# AS5600_AS5601.net
KiCad netlist of a schematic drawn in Altium Designer
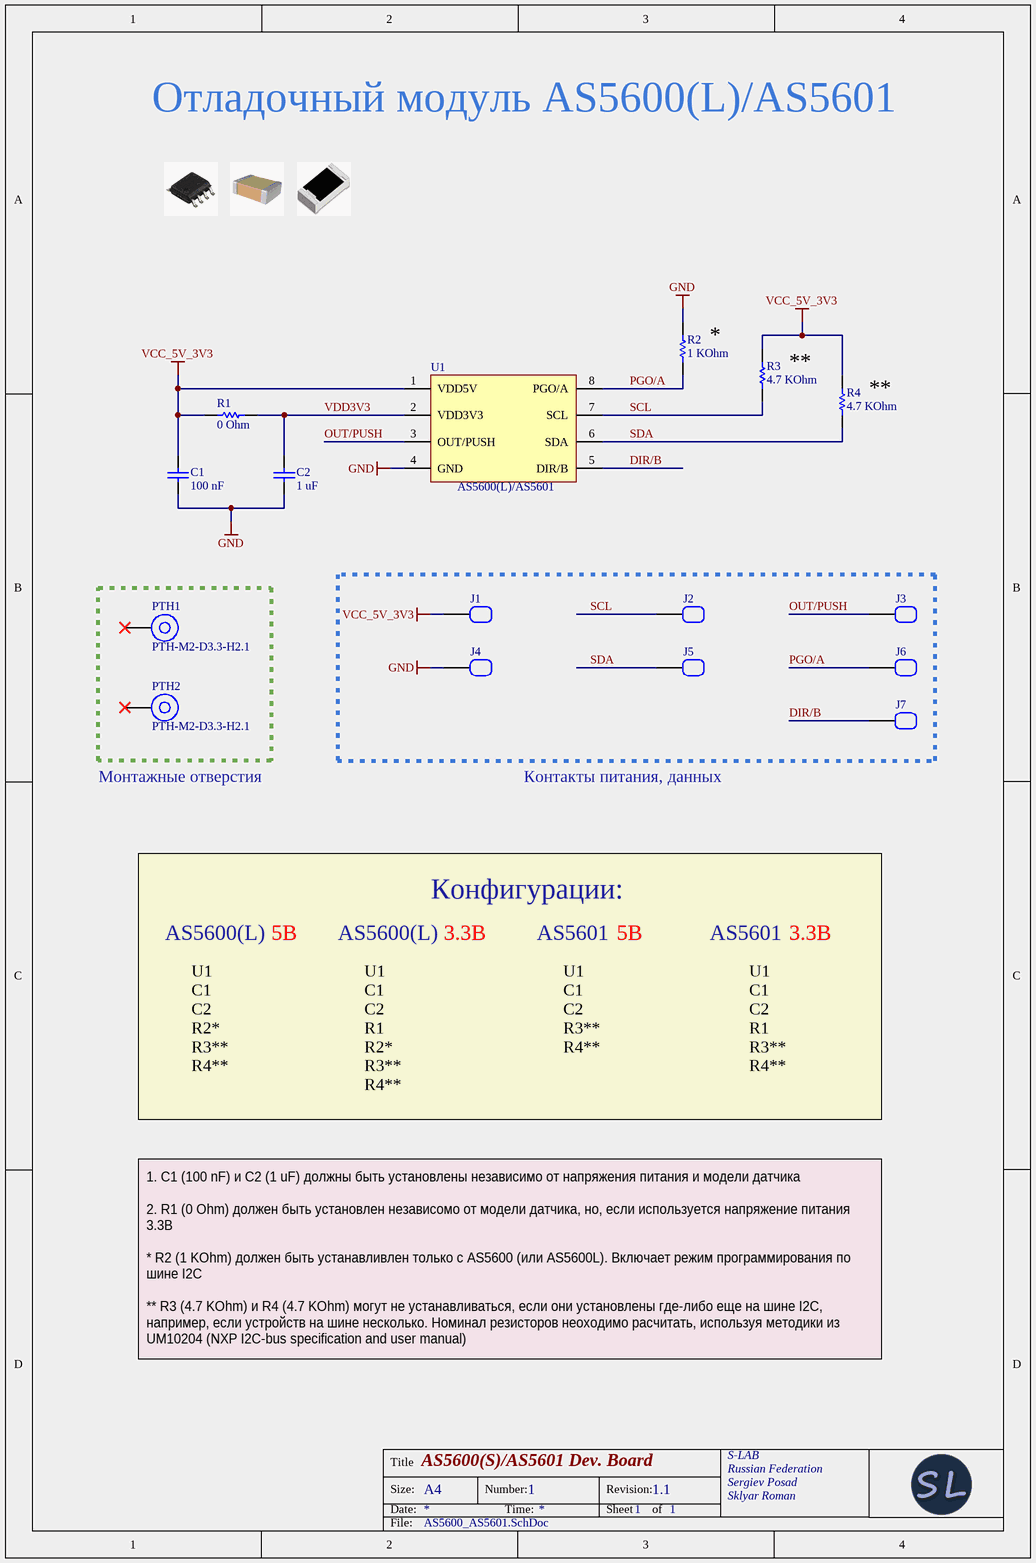
[diagram p0: AS5600_AS5601.SchDoc]

(export (version "E")
  (design (tool "Eeschema 10.0.6"))
  (components
    (comp (ref "C1")
      (value "CAP-100N")
      (footprint "CAPC0603")
      (description "Chip Capacitor, 100 nF, +/- 5%")
      (fields (field (name "TOLERANCE") "5 %") (field (name "CAPACITANCE") "100 nF"))
      (libsource (lib "Конденсаторы керамические SMD") (part "CAP-100N"))
    )
    (comp (ref "C2")
      (value "CAP-1U")
      (footprint "CAPC0603")
      (description "Chip Capacitor, 1 uF, +/- 5%")
      (fields (field (name "TOLERANCE") "5 %") (field (name "CAPACITANCE") "1 uF"))
      (libsource (lib "Конденсаторы керамические SMD") (part "CAP-1U"))
    )
    (comp (ref "J1") (value "Pad") (footprint "P_RR-1mm-2.5mm-50%") (libsource (lib "Разъемы") (part "Pad")))
    (comp (ref "J2") (value "Pad") (footprint "P_RR-1mm-2.5mm-50%") (libsource (lib "Разъемы") (part "Pad")))
    (comp (ref "J3") (value "Pad") (footprint "P_RR-1mm-2.5mm-50%") (libsource (lib "Разъемы") (part "Pad")))
    (comp (ref "J4") (value "Pad") (footprint "P_RR-1mm-2.5mm-50%") (libsource (lib "Разъемы") (part "Pad")))
    (comp (ref "J5") (value "Pad") (footprint "P_RR-1mm-2.5mm-50%") (libsource (lib "Разъемы") (part "Pad")))
    (comp (ref "J6") (value "Pad") (footprint "P_RR-1mm-2.5mm-50%") (libsource (lib "Разъемы") (part "Pad")))
    (comp (ref "J7") (value "Pad") (footprint "P_RR-1mm-2.5mm-50%") (libsource (lib "Разъемы") (part "Pad")))
    (comp (ref "PTH1")
      (value "PTH-M2-D3.3-H2.1")
      (footprint "PTH-M2-D4-H2.1")
      (libsource (lib "Разъемы") (part "PTH-M2-D4-H2.1"))
    )
    (comp (ref "PTH2")
      (value "PTH-M2-D3.3-H2.1")
      (footprint "PTH-M2-D4-H2.1")
      (libsource (lib "Разъемы") (part "PTH-M2-D4-H2.1"))
    )
    (comp (ref "R1")
      (value "RES-0")
      (footprint "RES0603")
      (description "Chip Resistor, 0 Ohm, +/- 1%")
      (fields (field (name "TOLERANCE") "1 %") (field (name "RESISTANCE") "0 Ohm"))
      (libsource (lib "Резисторы SMD") (part "RES-0"))
    )
    (comp (ref "R2")
      (value "RES-1K")
      (footprint "RES0603")
      (description "Chip Resistor, 1 KOhm, +/- 1%")
      (fields (field (name "TOLERANCE") "1 %") (field (name "RESISTANCE") "1 KOhm"))
      (libsource (lib "Резисторы SMD") (part "RES-1K"))
    )
    (comp (ref "R3")
      (value "RES-4K7")
      (footprint "RES0603")
      (description "Chip Resistor, 4.7 KOhm, +/- 1%")
      (fields (field (name "TOLERANCE") "1 %") (field (name "RESISTANCE") "4.7 KOhm"))
      (libsource (lib "Резисторы SMD") (part "RES-4K7"))
    )
    (comp (ref "R4")
      (value "RES-4K7")
      (footprint "RES0603")
      (description "Chip Resistor, 4.7 KOhm, +/- 1%")
      (fields (field (name "TOLERANCE") "1 %") (field (name "RESISTANCE") "4.7 KOhm"))
      (libsource (lib "Резисторы SMD") (part "RES-4K7"))
    )
    (comp (ref "U1")
      (value "AS5600(L)/AS5601")
      (footprint "SOIC-8-150")
      (description "12-bit on-axis magnetic rotary position sensor with analog or PWM output")
      (fields (field (name "PARTNUMBER") "AS5600"))
      (libsource (lib "Магнитные датчики") (part "AS5600"))
    )
  )
  (nets
    (net (code "1") (name "/DIR{slash}B") (class "Default")
      (node (ref "J7") (pin "1") (pintype "passive"))
      (node (ref "U1") (pin "5") (pinfunction "DIR/B_5") (pintype "passive"))
    )
    (net (code "2") (name "/OUT{slash}PUSH") (class "Default")
      (node (ref "J3") (pin "1") (pintype "passive"))
      (node (ref "U1") (pin "3") (pinfunction "OUT/PUSH_3") (pintype "passive"))
    )
    (net (code "3") (name "/PGO{slash}A") (class "Default")
      (node (ref "J6") (pin "1") (pintype "passive"))
      (node (ref "R2") (pin "1") (pinfunction "1_1") (pintype "passive"))
      (node (ref "U1") (pin "8") (pinfunction "PGO/A_8") (pintype "passive"))
    )
    (net (code "4") (name "/SCL") (class "Default")
      (node (ref "J2") (pin "1") (pintype "passive"))
      (node (ref "R3") (pin "1") (pinfunction "1_1") (pintype "passive"))
      (node (ref "U1") (pin "7") (pinfunction "SCL_7") (pintype "passive"))
    )
    (net (code "5") (name "/SDA") (class "Default")
      (node (ref "J5") (pin "1") (pintype "passive"))
      (node (ref "R4") (pin "1") (pinfunction "1_1") (pintype "passive"))
      (node (ref "U1") (pin "6") (pinfunction "SDA_6") (pintype "passive"))
    )
    (net (code "6") (name "/VDD3V3") (class "Default")
      (node (ref "C2") (pin "2") (pinfunction "2_2") (pintype "passive"))
      (node (ref "R1") (pin "1") (pinfunction "1_1") (pintype "passive"))
      (node (ref "U1") (pin "2") (pinfunction "VDD3V3_2") (pintype "passive"))
    )
    (net (code "7") (name "GND") (class "Default")
      (node (ref "C1") (pin "1") (pinfunction "1_1") (pintype "passive"))
      (node (ref "C2") (pin "1") (pinfunction "1_1") (pintype "passive"))
      (node (ref "J4") (pin "1") (pintype "passive"))
      (node (ref "R2") (pin "2") (pinfunction "2_2") (pintype "passive"))
      (node (ref "U1") (pin "4") (pinfunction "GND_4") (pintype "passive"))
    )
    (net (code "8") (name "VCC_5V_3V3") (class "Default")
      (node (ref "C1") (pin "2") (pinfunction "2_2") (pintype "passive"))
      (node (ref "J1") (pin "1") (pintype "passive"))
      (node (ref "R1") (pin "2") (pinfunction "2_2") (pintype "passive"))
      (node (ref "R3") (pin "2") (pinfunction "2_2") (pintype "passive"))
      (node (ref "R4") (pin "2") (pinfunction "2_2") (pintype "passive"))
      (node (ref "U1") (pin "1") (pinfunction "VDD5V_1") (pintype "passive"))
    )
    (net (code "9") (name "unconnected-(PTH1-PadPTH)") (class "Default")
      (node (ref "PTH1") (pin "PTH") (pintype "passive+no_connect"))
    )
    (net (code "10") (name "unconnected-(PTH2-PadPTH)") (class "Default")
      (node (ref "PTH2") (pin "PTH") (pintype "passive+no_connect"))
    )
  )
)
